# Sheet1.net
KiCad netlist of a schematic drawn in Altium Designer
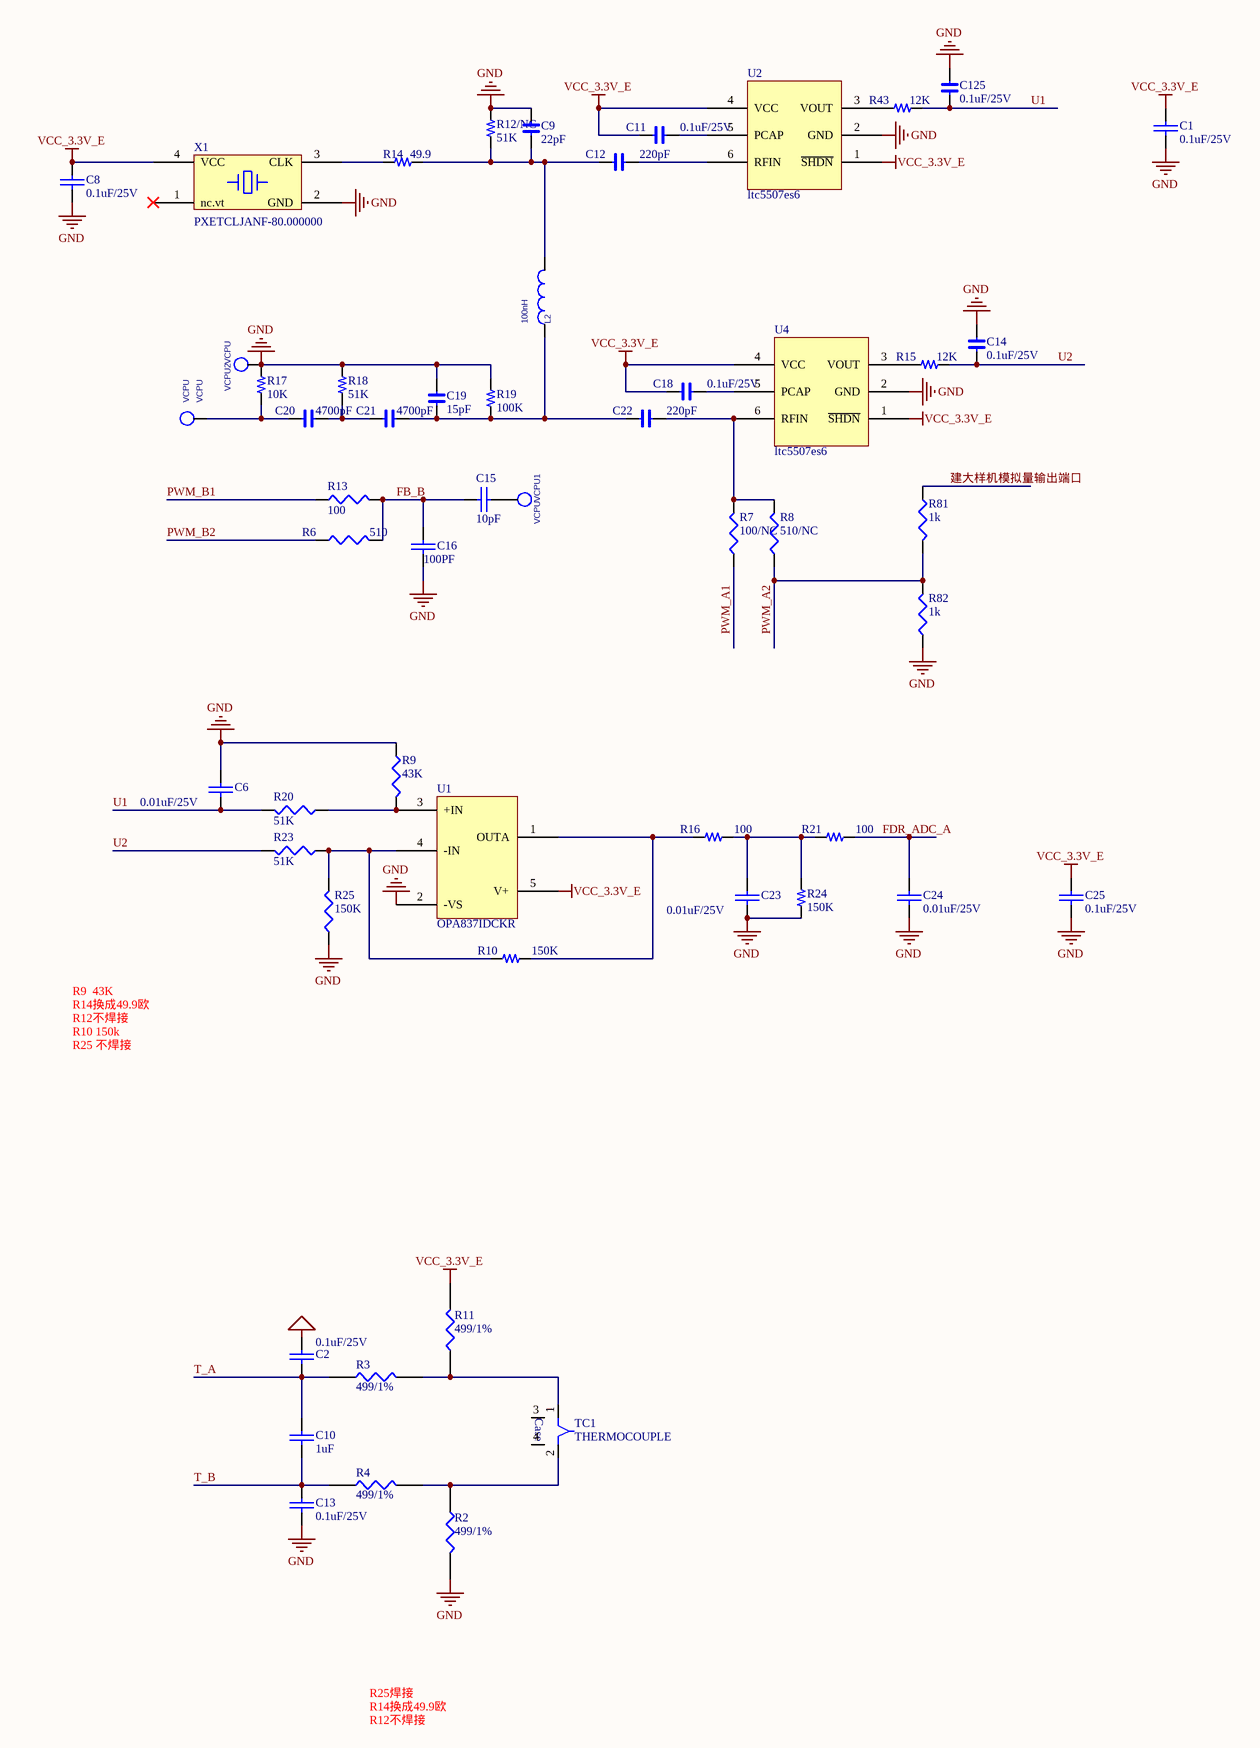
[diagram p0: Sheet1.SchDoc]

(export (version "E")
  (design (tool "Eeschema 10.0.6"))
  (components
    (comp (ref "C1")
      (value "0.1uF/25V")
      (footprint "0603C")
      (description "Capacitor")
      (libsource (lib "SM") (part "CAP"))
    )
    (comp (ref "C2")
      (value "0.1uF/25V")
      (footprint "0603c")
      (description "Capacitor")
      (libsource (lib "*") (part "CAP"))
    )
    (comp (ref "C6")
      (value "0.01uF/25V")
      (footprint "0603C")
      (description "Capacitor")
      (libsource (lib "SM") (part "CAP"))
    )
    (comp (ref "C8")
      (value "0.1uF/25V")
      (footprint "0603C")
      (description "Capacitor")
      (libsource (lib "SM") (part "CAP"))
    )
    (comp (ref "C9")
      (value "22pF")
      (footprint "0603C")
      (description "C")
      (libsource (lib "YxmSCH") (part "C"))
    )
    (comp (ref "C10")
      (value "1uF")
      (footprint "0603c")
      (description "Capacitor")
      (libsource (lib "*") (part "CAP"))
    )
    (comp (ref "C11")
      (value "0.1uF/25V")
      (footprint "0603C")
      (description "C")
      (libsource (lib "YxmSCH") (part "C"))
    )
    (comp (ref "C12")
      (value "220pF")
      (footprint "0603C")
      (description "C")
      (libsource (lib "YxmSCH") (part "C"))
    )
    (comp (ref "C13")
      (value "0.1uF/25V")
      (footprint "0603c")
      (description "Capacitor")
      (libsource (lib "*") (part "CAP"))
    )
    (comp (ref "C14")
      (value "0.1uF/25V")
      (footprint "0603C")
      (description "C")
      (libsource (lib "YxmSCH") (part "C"))
    )
    (comp (ref "C15")
      (value "10pF")
      (footprint "0603C")
      (description "Capacitor")
      (libsource (lib "SM") (part "CAP"))
    )
    (comp (ref "C16")
      (value "100PF")
      (footprint "0603C")
      (description "Capacitor")
      (libsource (lib "SM") (part "CAP"))
    )
    (comp (ref "C18")
      (value "0.1uF/25V")
      (footprint "0603C")
      (description "C")
      (libsource (lib "YxmSCH") (part "C"))
    )
    (comp (ref "C19")
      (value "15pF")
      (footprint "0603C")
      (description "C")
      (libsource (lib "YxmSCH") (part "C"))
    )
    (comp (ref "C20")
      (value "4700pF")
      (footprint "0603C")
      (description "C")
      (libsource (lib "YxmSCH") (part "C"))
    )
    (comp (ref "C21")
      (value "4700pF")
      (footprint "0603C")
      (description "C")
      (libsource (lib "YxmSCH") (part "C"))
    )
    (comp (ref "C22")
      (value "220pF")
      (footprint "0603C")
      (description "C")
      (libsource (lib "YxmSCH") (part "C"))
    )
    (comp (ref "C23")
      (value "0.01uF/25V")
      (footprint "0603C")
      (description "Capacitor")
      (libsource (lib "SM") (part "CAP"))
    )
    (comp (ref "C24")
      (value "0.01uF/25V")
      (footprint "0603C")
      (description "Capacitor")
      (libsource (lib "SM") (part "CAP"))
    )
    (comp (ref "C25")
      (value "0.1uF/25V")
      (footprint "0603C")
      (description "Capacitor")
      (libsource (lib "SM") (part "CAP"))
    )
    (comp (ref "C125")
      (value "0.1uF/25V")
      (footprint "0603C")
      (description "C")
      (libsource (lib "YxmSCH") (part "C"))
    )
    (comp (ref "L2") (value "100nH") (footprint "0603R") (libsource (lib "*") (part "INDUCTOR_1")))
    (comp (ref "R2") (value "499/1%") (footprint "0603r") (libsource (lib "*") (part "RES1")))
    (comp (ref "R3") (value "499/1%") (footprint "0603r") (libsource (lib "*") (part "RES1")))
    (comp (ref "R4") (value "499/1%") (footprint "0603r") (libsource (lib "*") (part "RES1")))
    (comp (ref "R6")
      (value "510")
      (footprint "0603R")
      (description "Resistor")
      (fields (field (name "PUBLISHER") "Altium Limited"))
      (libsource (lib "SM") (part "Res3"))
    )
    (comp (ref "R7")
      (value "100/NC")
      (footprint "0603R")
      (description "Resistor")
      (fields (field (name "PUBLISHER") "Altium Limited"))
      (libsource (lib "SM") (part "Res3"))
    )
    (comp (ref "R8")
      (value "510/NC")
      (footprint "0603R")
      (description "Resistor")
      (fields (field (name "PUBLISHER") "Altium Limited"))
      (libsource (lib "SM") (part "Res3"))
    )
    (comp (ref "R9")
      (value "43K")
      (footprint "0603R")
      (description "Resistor")
      (fields (field (name "PUBLISHER") "Altium Limited"))
      (libsource (lib "SM") (part "Res3"))
    )
    (comp (ref "R10")
      (value "150K")
      (footprint "0603R")
      (description "R")
      (libsource (lib "JRJ_1") (part "R"))
    )
    (comp (ref "R11") (value "499/1%") (footprint "0603r") (libsource (lib "*") (part "RES1")))
    (comp (ref "R12/NC")
      (value "51K")
      (footprint "0603r")
      (description "R")
      (libsource (lib "JRJ") (part "R"))
    )
    (comp (ref "R13")
      (value "100")
      (footprint "0603R")
      (description "Resistor")
      (fields (field (name "PUBLISHER") "Altium Limited"))
      (libsource (lib "SM") (part "Res3"))
    )
    (comp (ref "R14") (value "49.9") (footprint "0603r") (description "R") (libsource (lib "JRJ") (part "R")))
    (comp (ref "R15") (value "12K") (footprint "0603r") (description "R") (libsource (lib "JRJ") (part "R")))
    (comp (ref "R16")
      (value "100")
      (footprint "0603R")
      (description "R")
      (libsource (lib "JRJ_1") (part "R"))
    )
    (comp (ref "R17") (value "10K") (footprint "0603r") (description "R") (libsource (lib "JRJ") (part "R")))
    (comp (ref "R18") (value "51K") (footprint "0603r") (description "R") (libsource (lib "JRJ") (part "R")))
    (comp (ref "R19") (value "100K") (footprint "0603r") (description "R") (libsource (lib "JRJ") (part "R")))
    (comp (ref "R20")
      (value "51K")
      (footprint "0603R")
      (description "Resistor")
      (fields (field (name "PUBLISHER") "Altium Limited"))
      (libsource (lib "SM") (part "Res3"))
    )
    (comp (ref "R21")
      (value "100")
      (footprint "0603R")
      (description "R")
      (libsource (lib "JRJ_1") (part "R"))
    )
    (comp (ref "R23")
      (value "51K")
      (footprint "0603R")
      (description "Resistor")
      (fields (field (name "PUBLISHER") "Altium Limited"))
      (libsource (lib "SM") (part "Res3"))
    )
    (comp (ref "R24")
      (value "150K")
      (footprint "0603R")
      (description "R")
      (libsource (lib "JRJ_1") (part "R"))
    )
    (comp (ref "R25")
      (value "150K")
      (footprint "0603R")
      (description "Resistor")
      (fields (field (name "PUBLISHER") "Altium Limited"))
      (libsource (lib "SM") (part "Res3"))
    )
    (comp (ref "R43") (value "12K") (footprint "0603r") (description "R") (libsource (lib "JRJ") (part "R")))
    (comp (ref "R81")
      (value "1k")
      (footprint "0603R")
      (description "Resistor")
      (fields (field (name "PUBLISHER") "Altium Limited"))
      (libsource (lib "SM") (part "Res3"))
    )
    (comp (ref "R82")
      (value "1k")
      (footprint "0603R")
      (description "Resistor")
      (fields (field (name "PUBLISHER") "Altium Limited"))
      (libsource (lib "SM") (part "Res3"))
    )
    (comp (ref "TC1") (value "THERMOCOUPLE") (footprint "0603R") (libsource (lib "*") (part "THERMOCOUPLE")))
    (comp (ref "U1")
      (value "OPA837IDCKR")
      (footprint "SC70-5")
      (libsource (lib "Schlib_20110825") (part "OPA837 DCK"))
    )
    (comp (ref "U2") (value "ltc5507es6") (footprint "SOT23-6") (libsource (lib "stm32") (part "ltc5507es6")))
    (comp (ref "U4") (value "ltc5507es6") (footprint "SOT23-6") (libsource (lib "stm32") (part "ltc5507es6")))
    (comp (ref "VCPU") (value "VCPU") (footprint "probe") (libsource (lib "*") (part "T_POINT_R")))
    (comp (ref "VCPU1") (value "VCPU") (footprint "probe") (libsource (lib "*") (part "T_POINT_R")))
    (comp (ref "VCPU2") (value "VCPU") (footprint "probe") (libsource (lib "*") (part "T_POINT_R")))
    (comp (ref "X1")
      (value "PXETCLJANF-80.000000")
      (footprint "XTAL4TN_7050")
      (libsource (lib "Y0801_V13") (part "XTAL4S"))
    )
  )
  (nets
    (net (code "1") (name "/FB_B") (class "Default")
      (node (ref "C15") (pin "1") (pinfunction "1_1") (pintype "passive"))
      (node (ref "C16") (pin "1") (pinfunction "1_1") (pintype "passive"))
      (node (ref "R13") (pin "2") (pinfunction "2_2") (pintype "passive"))
      (node (ref "R6") (pin "2") (pinfunction "2_2") (pintype "passive"))
    )
    (net (code "2") (name "/FDR_ADC_A") (class "Default")
      (node (ref "C24") (pin "2") (pinfunction "2_2") (pintype "passive"))
      (node (ref "R21") (pin "2") (pintype "passive"))
    )
    (net (code "3") (name "/PWM_A1") (class "Default")
      (node (ref "R7") (pin "1") (pinfunction "1_1") (pintype "passive"))
    )
    (net (code "4") (name "/PWM_A2") (class "Default")
      (node (ref "R8") (pin "1") (pinfunction "1_1") (pintype "passive"))
      (node (ref "R81") (pin "2") (pinfunction "2_2") (pintype "passive"))
      (node (ref "R82") (pin "2") (pinfunction "2_2") (pintype "passive"))
    )
    (net (code "5") (name "/PWM_B1") (class "Default")
      (node (ref "R13") (pin "1") (pinfunction "1_1") (pintype "passive"))
    )
    (net (code "6") (name "/PWM_B2") (class "Default")
      (node (ref "R6") (pin "1") (pinfunction "1_1") (pintype "passive"))
    )
    (net (code "7") (name "/T_A") (class "Default")
      (node (ref "C10") (pin "1") (pinfunction "1_1") (pintype "passive"))
      (node (ref "C2") (pin "1") (pinfunction "1_1") (pintype "passive"))
      (node (ref "R3") (pin "1") (pinfunction "1_1") (pintype "passive"))
    )
    (net (code "8") (name "/T_B") (class "Default")
      (node (ref "C10") (pin "2") (pinfunction "2_2") (pintype "passive"))
      (node (ref "C13") (pin "1") (pinfunction "1_1") (pintype "passive"))
      (node (ref "R4") (pin "1") (pinfunction "1_1") (pintype "passive"))
    )
    (net (code "9") (name "/U1") (class "Default")
      (node (ref "C125") (pin "1") (pintype "passive"))
      (node (ref "C6") (pin "1") (pinfunction "1_1") (pintype "passive"))
      (node (ref "R20") (pin "2") (pinfunction "2_2") (pintype "passive"))
      (node (ref "R43") (pin "1") (pintype "passive"))
    )
    (net (code "10") (name "/U2") (class "Default")
      (node (ref "C14") (pin "1") (pintype "passive"))
      (node (ref "R15") (pin "1") (pintype "passive"))
      (node (ref "R23") (pin "2") (pinfunction "2_2") (pintype "passive"))
    )
    (net (code "11") (name "/建大样机模拟量输出端口") (class "Default")
      (node (ref "R81") (pin "1") (pinfunction "1_1") (pintype "passive"))
    )
    (net (code "12") (name "GND") (class "Default")
      (node (ref "C1") (pin "1") (pinfunction "1_1") (pintype "passive"))
      (node (ref "C125") (pin "2") (pintype "passive"))
      (node (ref "C13") (pin "2") (pinfunction "2_2") (pintype "passive"))
      (node (ref "C14") (pin "2") (pintype "passive"))
      (node (ref "C16") (pin "2") (pinfunction "2_2") (pintype "passive"))
      (node (ref "C19") (pin "2") (pintype "passive"))
      (node (ref "C2") (pin "2") (pinfunction "2_2") (pintype "passive"))
      (node (ref "C23") (pin "1") (pinfunction "1_1") (pintype "passive"))
      (node (ref "C24") (pin "1") (pinfunction "1_1") (pintype "passive"))
      (node (ref "C25") (pin "1") (pinfunction "1_1") (pintype "passive"))
      (node (ref "C6") (pin "2") (pinfunction "2_2") (pintype "passive"))
      (node (ref "C8") (pin "2") (pinfunction "2_2") (pintype "passive"))
      (node (ref "C9") (pin "1") (pintype "passive"))
      (node (ref "R12/NC") (pin "2") (pintype "passive"))
      (node (ref "R17") (pin "2") (pintype "passive"))
      (node (ref "R18") (pin "2") (pintype "passive"))
      (node (ref "R19") (pin "2") (pintype "passive"))
      (node (ref "R2") (pin "2") (pinfunction "2_2") (pintype "passive"))
      (node (ref "R24") (pin "1") (pintype "passive"))
      (node (ref "R25") (pin "1") (pinfunction "1_1") (pintype "passive"))
      (node (ref "R82") (pin "1") (pinfunction "1_1") (pintype "passive"))
      (node (ref "R9") (pin "1") (pinfunction "1_1") (pintype "passive"))
      (node (ref "U1") (pin "2") (pinfunction "-VS_2") (pintype "passive"))
      (node (ref "U2") (pin "2") (pinfunction "GND_2") (pintype "passive"))
      (node (ref "U4") (pin "2") (pinfunction "GND_2") (pintype "passive"))
      (node (ref "VCPU2") (pin "1") (pinfunction "TP_1") (pintype "passive"))
      (node (ref "X1") (pin "2") (pinfunction "GND_2") (pintype "power_in"))
    )
    (net (code "13") (name "Net-(C12-Pad1)") (class "Default")
      (node (ref "C12") (pin "1") (pintype "passive"))
      (node (ref "C9") (pin "2") (pintype "passive"))
      (node (ref "L2") (pin "2") (pinfunction "2_2") (pintype "passive"))
      (node (ref "R12/NC") (pin "1") (pintype "passive"))
      (node (ref "R14") (pin "2") (pintype "passive"))
    )
    (net (code "14") (name "Net-(C19-Pad1)") (class "Default")
      (node (ref "C19") (pin "1") (pintype "passive"))
      (node (ref "C21") (pin "2") (pintype "passive"))
      (node (ref "C22") (pin "1") (pintype "passive"))
      (node (ref "L2") (pin "1") (pinfunction "1_1") (pintype "passive"))
      (node (ref "R19") (pin "1") (pintype "passive"))
    )
    (net (code "15") (name "Net-(C20-Pad2)") (class "Default")
      (node (ref "C20") (pin "2") (pintype "passive"))
      (node (ref "C21") (pin "1") (pintype "passive"))
      (node (ref "R18") (pin "1") (pintype "passive"))
    )
    (net (code "16") (name "Net-(C23-Pad2)") (class "Default")
      (node (ref "C23") (pin "2") (pinfunction "2_2") (pintype "passive"))
      (node (ref "R16") (pin "2") (pintype "passive"))
      (node (ref "R21") (pin "1") (pintype "passive"))
      (node (ref "R24") (pin "2") (pintype "passive"))
    )
    (net (code "17") (name "Net-(R2-Pad1)") (class "Default")
      (node (ref "R2") (pin "1") (pinfunction "1_1") (pintype "passive"))
      (node (ref "R4") (pin "2") (pinfunction "2_2") (pintype "passive"))
      (node (ref "TC1") (pin "2") (pinfunction "2_2") (pintype "passive"))
    )
    (net (code "18") (name "Net-(R11-Pad1)") (class "Default")
      (node (ref "R11") (pin "1") (pinfunction "1_1") (pintype "passive"))
      (node (ref "R3") (pin "2") (pinfunction "2_2") (pintype "passive"))
      (node (ref "TC1") (pin "1") (pinfunction "1_1") (pintype "passive"))
    )
    (net (code "19") (name "Net-(U1-+IN)") (class "Default")
      (node (ref "R20") (pin "1") (pinfunction "1_1") (pintype "passive"))
      (node (ref "R9") (pin "2") (pinfunction "2_2") (pintype "passive"))
      (node (ref "U1") (pin "3") (pinfunction "+IN_3") (pintype "passive"))
    )
    (net (code "20") (name "Net-(U1--IN)") (class "Default")
      (node (ref "R10") (pin "1") (pintype "passive"))
      (node (ref "R23") (pin "1") (pinfunction "1_1") (pintype "passive"))
      (node (ref "R25") (pin "2") (pinfunction "2_2") (pintype "passive"))
      (node (ref "U1") (pin "4") (pinfunction "-IN_4") (pintype "passive"))
    )
    (net (code "21") (name "Net-(U1-OUTA)") (class "Default")
      (node (ref "R10") (pin "2") (pintype "passive"))
      (node (ref "R16") (pin "1") (pintype "passive"))
      (node (ref "U1") (pin "1") (pinfunction "OUTA_1") (pintype "passive"))
    )
    (net (code "22") (name "Net-(U2-PCAP)") (class "Default")
      (node (ref "C11") (pin "2") (pintype "passive"))
      (node (ref "U2") (pin "5") (pinfunction "PCAP_5") (pintype "passive"))
    )
    (net (code "23") (name "Net-(U2-RFIN)") (class "Default")
      (node (ref "C12") (pin "2") (pintype "passive"))
      (node (ref "U2") (pin "6") (pinfunction "RFIN_6") (pintype "passive"))
    )
    (net (code "24") (name "Net-(U2-VOUT)") (class "Default")
      (node (ref "R43") (pin "2") (pintype "passive"))
      (node (ref "U2") (pin "3") (pinfunction "VOUT_3") (pintype "passive"))
    )
    (net (code "25") (name "Net-(U4-PCAP)") (class "Default")
      (node (ref "C18") (pin "2") (pintype "passive"))
      (node (ref "U4") (pin "5") (pinfunction "PCAP_5") (pintype "passive"))
    )
    (net (code "26") (name "Net-(U4-RFIN)") (class "Default")
      (node (ref "C22") (pin "2") (pintype "passive"))
      (node (ref "R7") (pin "2") (pinfunction "2_2") (pintype "passive"))
      (node (ref "R8") (pin "2") (pinfunction "2_2") (pintype "passive"))
      (node (ref "U4") (pin "6") (pinfunction "RFIN_6") (pintype "passive"))
    )
    (net (code "27") (name "Net-(U4-VOUT)") (class "Default")
      (node (ref "R15") (pin "2") (pintype "passive"))
      (node (ref "U4") (pin "3") (pinfunction "VOUT_3") (pintype "passive"))
    )
    (net (code "28") (name "Net-(VCPU-TP)") (class "Default")
      (node (ref "C20") (pin "1") (pintype "passive"))
      (node (ref "R17") (pin "1") (pintype "passive"))
      (node (ref "VCPU") (pin "1") (pinfunction "TP_1") (pintype "passive"))
    )
    (net (code "29") (name "Net-(VCPU1-TP)") (class "Default")
      (node (ref "C15") (pin "2") (pinfunction "2_2") (pintype "passive"))
      (node (ref "VCPU1") (pin "1") (pinfunction "TP_1") (pintype "passive"))
    )
    (net (code "30") (name "Net-(X1-CLK)") (class "Default")
      (node (ref "R14") (pin "1") (pintype "passive"))
      (node (ref "X1") (pin "3") (pinfunction "CLK_3") (pintype "passive"))
    )
    (net (code "31") (name "VCC_3.3V_E") (class "Default")
      (node (ref "C1") (pin "2") (pinfunction "2_2") (pintype "passive"))
      (node (ref "C11") (pin "1") (pintype "passive"))
      (node (ref "C18") (pin "1") (pintype "passive"))
      (node (ref "C25") (pin "2") (pinfunction "2_2") (pintype "passive"))
      (node (ref "C8") (pin "1") (pinfunction "1_1") (pintype "passive"))
      (node (ref "R11") (pin "2") (pinfunction "2_2") (pintype "passive"))
      (node (ref "U1") (pin "5") (pinfunction "V+_5") (pintype "passive"))
      (node (ref "U2") (pin "1") (pinfunction "~{SHDN}_1") (pintype "passive"))
      (node (ref "U2") (pin "4") (pinfunction "VCC_4") (pintype "passive"))
      (node (ref "U4") (pin "1") (pinfunction "~{SHDN}_1") (pintype "passive"))
      (node (ref "U4") (pin "4") (pinfunction "VCC_4") (pintype "passive"))
      (node (ref "X1") (pin "4") (pinfunction "VCC_4") (pintype "power_in"))
    )
    (net (code "32") (name "unconnected-(TC1-Pad3)") (class "Default")
      (node (ref "TC1") (pin "3") (pinfunction "3_3") (pintype "passive"))
    )
    (net (code "33") (name "unconnected-(TC1-Pad4)") (class "Default")
      (node (ref "TC1") (pin "4") (pinfunction "4_4") (pintype "passive"))
    )
    (net (code "34") (name "unconnected-(X1-nc.vt-Pad1)") (class "Default")
      (node (ref "X1") (pin "1") (pinfunction "nc.vt_1") (pintype "passive+no_connect"))
    )
  )
)
